# zero-hm-10-breakout.net
KiCad netlist of a schematic drawn in EAGLE
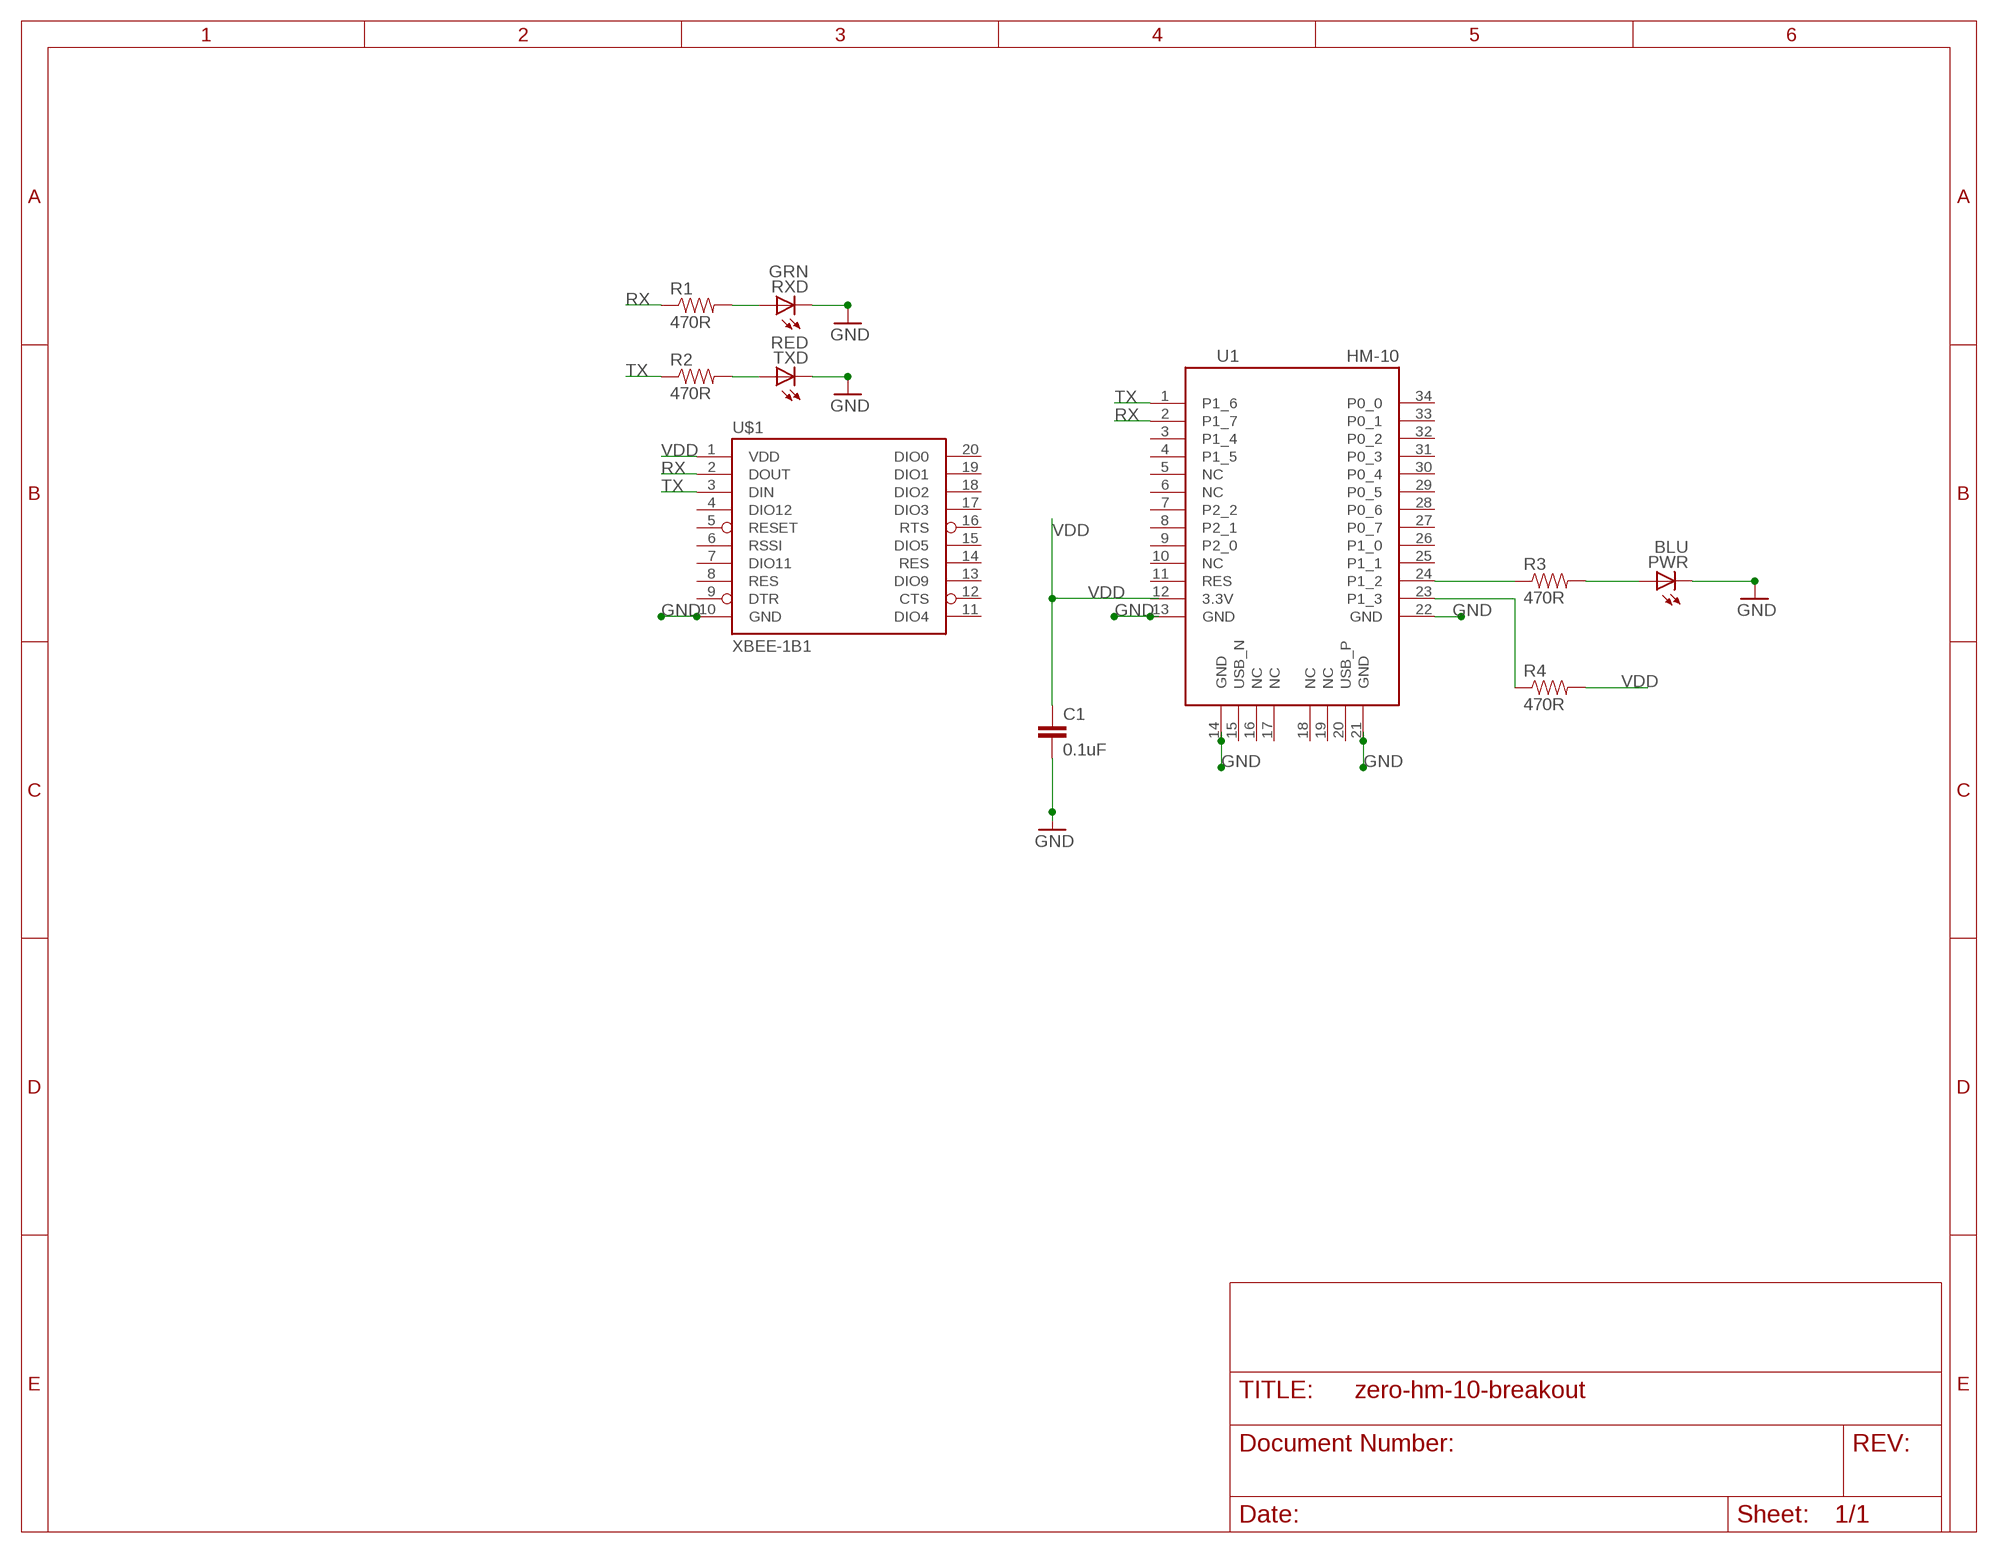
[diagram p0: schematic, sheet 1]

(export (version "E")
  (design (tool "Eeschema 10.0.6"))
  (components
    (comp (ref "C1")
      (value "0.1uF")
      (footprint "eagle-import:0603-CAP")
      (libsource (lib "eagle-import") (part "0.1UF-25V(+80/-20%)(0603)"))
    )
    (comp (ref "PWR")
      (value "BLU")
      (footprint "eagle-import:CHIPLED_0805")
      (libsource (lib "eagle-import") (part "LEDCHIPLED_0805"))
    )
    (comp (ref "R1")
      (value "470R")
      (footprint "eagle-import:0805")
      (libsource (lib "eagle-import") (part "0.3OHM-1/8W-1%(0805)"))
    )
    (comp (ref "R2")
      (value "470R")
      (footprint "eagle-import:0805")
      (libsource (lib "eagle-import") (part "0.3OHM-1/8W-1%(0805)"))
    )
    (comp (ref "R3")
      (value "470R")
      (footprint "eagle-import:0805")
      (libsource (lib "eagle-import") (part "0.3OHM-1/8W-1%(0805)"))
    )
    (comp (ref "R4")
      (value "470R")
      (footprint "eagle-import:0805")
      (libsource (lib "eagle-import") (part "0.3OHM-1/8W-1%(0805)"))
    )
    (comp (ref "RXD")
      (value "GRN")
      (footprint "eagle-import:CHIPLED_0805")
      (libsource (lib "eagle-import") (part "LEDCHIPLED_0805"))
    )
    (comp (ref "TXD")
      (value "RED")
      (footprint "eagle-import:CHIPLED_0805")
      (libsource (lib "eagle-import") (part "LEDCHIPLED_0805"))
    )
    (comp (ref "U$1")
      (value "XBEE-1B1")
      (footprint "eagle-import:XBEE-1")
      (libsource (lib "eagle-import") (part "XBEE-1B1"))
    )
    (comp (ref "U1")
      (value "HM-10")
      (footprint "eagle-import:HM-10")
      (libsource (lib "eagle-import") (part "HM-10"))
    )
  )
  (nets
    (net (code "1") (name "/RX") (class "Default")
      (node (ref "R1") (pin "1") (pinfunction "1_1") (pintype "passive"))
      (node (ref "U$1") (pin "2") (pinfunction "DOUT_2") (pintype "output"))
      (node (ref "U1") (pin "2") (pinfunction "P1_7_2") (pintype "bidirectional"))
    )
    (net (code "2") (name "/TX") (class "Default")
      (node (ref "R2") (pin "1") (pinfunction "1_1") (pintype "passive"))
      (node (ref "U$1") (pin "3") (pinfunction "DIN_3") (pintype "input"))
      (node (ref "U1") (pin "1") (pinfunction "P1_6_1") (pintype "bidirectional"))
    )
    (net (code "3") (name "/VDD") (class "Default")
      (node (ref "C1") (pin "1") (pinfunction "1_1") (pintype "passive"))
      (node (ref "R4") (pin "2") (pinfunction "2_2") (pintype "passive"))
      (node (ref "U$1") (pin "1") (pinfunction "VDD_1") (pintype "power_in"))
      (node (ref "U1") (pin "12") (pinfunction "3.3V_12") (pintype "bidirectional"))
    )
    (net (code "4") (name "GND") (class "Default")
      (node (ref "C1") (pin "2") (pinfunction "2_2") (pintype "passive"))
      (node (ref "PWR") (pin "C") (pinfunction "C_C") (pintype "passive"))
      (node (ref "RXD") (pin "C") (pinfunction "C_C") (pintype "passive"))
      (node (ref "TXD") (pin "C") (pinfunction "C_C") (pintype "passive"))
      (node (ref "U$1") (pin "10") (pinfunction "GND_10") (pintype "power_in"))
      (node (ref "U1") (pin "13") (pinfunction "GND_13") (pintype "bidirectional"))
      (node (ref "U1") (pin "14") (pinfunction "GND_14") (pintype "bidirectional"))
      (node (ref "U1") (pin "21") (pinfunction "GND_21") (pintype "bidirectional"))
      (node (ref "U1") (pin "22") (pinfunction "GND_22") (pintype "bidirectional"))
    )
    (net (code "5") (name "Net-(PWR-PadA)") (class "Default")
      (node (ref "PWR") (pin "A") (pinfunction "A_A") (pintype "passive"))
      (node (ref "R3") (pin "2") (pinfunction "2_2") (pintype "passive"))
    )
    (net (code "6") (name "Net-(R1-Pad2)") (class "Default")
      (node (ref "R1") (pin "2") (pinfunction "2_2") (pintype "passive"))
      (node (ref "RXD") (pin "A") (pinfunction "A_A") (pintype "passive"))
    )
    (net (code "7") (name "Net-(R2-Pad2)") (class "Default")
      (node (ref "R2") (pin "2") (pinfunction "2_2") (pintype "passive"))
      (node (ref "TXD") (pin "A") (pinfunction "A_A") (pintype "passive"))
    )
    (net (code "8") (name "Net-(U1-P1_2)") (class "Default")
      (node (ref "R3") (pin "1") (pinfunction "1_1") (pintype "passive"))
      (node (ref "U1") (pin "24") (pinfunction "P1_2_24") (pintype "bidirectional"))
    )
    (net (code "9") (name "Net-(U1-P1_3)") (class "Default")
      (node (ref "R4") (pin "1") (pinfunction "1_1") (pintype "passive"))
      (node (ref "U1") (pin "23") (pinfunction "P1_3_23") (pintype "bidirectional"))
    )
    (net (code "10") (name "unconnected-(U$1-CTS-Pad12)") (class "Default")
      (node (ref "U$1") (pin "12") (pinfunction "CTS_12") (pintype "output"))
    )
    (net (code "11") (name "unconnected-(U$1-DIO0-Pad20)") (class "Default")
      (node (ref "U$1") (pin "20") (pinfunction "DIO0_20") (pintype "bidirectional"))
    )
    (net (code "12") (name "unconnected-(U$1-DIO1-Pad19)") (class "Default")
      (node (ref "U$1") (pin "19") (pinfunction "DIO1_19") (pintype "bidirectional"))
    )
    (net (code "13") (name "unconnected-(U$1-DIO2-Pad18)") (class "Default")
      (node (ref "U$1") (pin "18") (pinfunction "DIO2_18") (pintype "bidirectional"))
    )
    (net (code "14") (name "unconnected-(U$1-DIO3-Pad17)") (class "Default")
      (node (ref "U$1") (pin "17") (pinfunction "DIO3_17") (pintype "bidirectional"))
    )
    (net (code "15") (name "unconnected-(U$1-DIO4-Pad11)") (class "Default")
      (node (ref "U$1") (pin "11") (pinfunction "DIO4_11") (pintype "bidirectional"))
    )
    (net (code "16") (name "unconnected-(U$1-DIO5-Pad15)") (class "Default")
      (node (ref "U$1") (pin "15") (pinfunction "DIO5_15") (pintype "bidirectional"))
    )
    (net (code "17") (name "unconnected-(U$1-DIO9-Pad13)") (class "Default")
      (node (ref "U$1") (pin "13") (pinfunction "DIO9_13") (pintype "bidirectional"))
    )
    (net (code "18") (name "unconnected-(U$1-DIO11-Pad7)") (class "Default")
      (node (ref "U$1") (pin "7") (pinfunction "DIO11_7") (pintype "bidirectional"))
    )
    (net (code "19") (name "unconnected-(U$1-DIO12-Pad4)") (class "Default")
      (node (ref "U$1") (pin "4") (pinfunction "DIO12_4") (pintype "bidirectional"))
    )
    (net (code "20") (name "unconnected-(U$1-DTR-Pad9)") (class "Default")
      (node (ref "U$1") (pin "9") (pinfunction "DTR_9") (pintype "bidirectional"))
    )
    (net (code "21") (name "unconnected-(U$1-RES-Pad8)") (class "Default")
      (node (ref "U$1") (pin "8") (pinfunction "RES_8") (pintype "bidirectional"))
    )
    (net (code "22") (name "unconnected-(U$1-RES-Pad14)") (class "Default")
      (node (ref "U$1") (pin "14") (pinfunction "RES_14") (pintype "bidirectional"))
    )
    (net (code "23") (name "unconnected-(U$1-RESET-Pad5)") (class "Default")
      (node (ref "U$1") (pin "5") (pinfunction "RESET_5") (pintype "input"))
    )
    (net (code "24") (name "unconnected-(U$1-RSSI-Pad6)") (class "Default")
      (node (ref "U$1") (pin "6") (pinfunction "RSSI_6") (pintype "bidirectional"))
    )
    (net (code "25") (name "unconnected-(U$1-RTS-Pad16)") (class "Default")
      (node (ref "U$1") (pin "16") (pinfunction "RTS_16") (pintype "input"))
    )
    (net (code "26") (name "unconnected-(U1-NC-Pad5)") (class "Default")
      (node (ref "U1") (pin "5") (pinfunction "NC_5") (pintype "bidirectional"))
    )
    (net (code "27") (name "unconnected-(U1-NC-Pad6)") (class "Default")
      (node (ref "U1") (pin "6") (pinfunction "NC_6") (pintype "bidirectional"))
    )
    (net (code "28") (name "unconnected-(U1-NC-Pad10)") (class "Default")
      (node (ref "U1") (pin "10") (pinfunction "NC_10") (pintype "bidirectional"))
    )
    (net (code "29") (name "unconnected-(U1-NC-Pad16)") (class "Default")
      (node (ref "U1") (pin "16") (pinfunction "NC_16") (pintype "bidirectional"))
    )
    (net (code "30") (name "unconnected-(U1-NC-Pad17)") (class "Default")
      (node (ref "U1") (pin "17") (pinfunction "NC_17") (pintype "bidirectional"))
    )
    (net (code "31") (name "unconnected-(U1-NC-Pad18)") (class "Default")
      (node (ref "U1") (pin "18") (pinfunction "NC_18") (pintype "bidirectional"))
    )
    (net (code "32") (name "unconnected-(U1-NC-Pad19)") (class "Default")
      (node (ref "U1") (pin "19") (pinfunction "NC_19") (pintype "bidirectional"))
    )
    (net (code "33") (name "unconnected-(U1-P0_0-Pad34)") (class "Default")
      (node (ref "U1") (pin "34") (pinfunction "P0_0_34") (pintype "bidirectional"))
    )
    (net (code "34") (name "unconnected-(U1-P0_1-Pad33)") (class "Default")
      (node (ref "U1") (pin "33") (pinfunction "P0_1_33") (pintype "bidirectional"))
    )
    (net (code "35") (name "unconnected-(U1-P0_2-Pad32)") (class "Default")
      (node (ref "U1") (pin "32") (pinfunction "P0_2_32") (pintype "bidirectional"))
    )
    (net (code "36") (name "unconnected-(U1-P0_3-Pad31)") (class "Default")
      (node (ref "U1") (pin "31") (pinfunction "P0_3_31") (pintype "bidirectional"))
    )
    (net (code "37") (name "unconnected-(U1-P0_4-Pad30)") (class "Default")
      (node (ref "U1") (pin "30") (pinfunction "P0_4_30") (pintype "bidirectional"))
    )
    (net (code "38") (name "unconnected-(U1-P0_5-Pad29)") (class "Default")
      (node (ref "U1") (pin "29") (pinfunction "P0_5_29") (pintype "bidirectional"))
    )
    (net (code "39") (name "unconnected-(U1-P0_6-Pad28)") (class "Default")
      (node (ref "U1") (pin "28") (pinfunction "P0_6_28") (pintype "bidirectional"))
    )
    (net (code "40") (name "unconnected-(U1-P0_7-Pad27)") (class "Default")
      (node (ref "U1") (pin "27") (pinfunction "P0_7_27") (pintype "bidirectional"))
    )
    (net (code "41") (name "unconnected-(U1-P1_0-Pad26)") (class "Default")
      (node (ref "U1") (pin "26") (pinfunction "P1_0_26") (pintype "bidirectional"))
    )
    (net (code "42") (name "unconnected-(U1-P1_1-Pad25)") (class "Default")
      (node (ref "U1") (pin "25") (pinfunction "P1_1_25") (pintype "bidirectional"))
    )
    (net (code "43") (name "unconnected-(U1-P1_4-Pad3)") (class "Default")
      (node (ref "U1") (pin "3") (pinfunction "P1_4_3") (pintype "bidirectional"))
    )
    (net (code "44") (name "unconnected-(U1-P1_5-Pad4)") (class "Default")
      (node (ref "U1") (pin "4") (pinfunction "P1_5_4") (pintype "bidirectional"))
    )
    (net (code "45") (name "unconnected-(U1-P2_0-Pad9)") (class "Default")
      (node (ref "U1") (pin "9") (pinfunction "P2_0_9") (pintype "bidirectional"))
    )
    (net (code "46") (name "unconnected-(U1-P2_1-Pad8)") (class "Default")
      (node (ref "U1") (pin "8") (pinfunction "P2_1_8") (pintype "bidirectional"))
    )
    (net (code "47") (name "unconnected-(U1-P2_2-Pad7)") (class "Default")
      (node (ref "U1") (pin "7") (pinfunction "P2_2_7") (pintype "bidirectional"))
    )
    (net (code "48") (name "unconnected-(U1-RES-Pad11)") (class "Default")
      (node (ref "U1") (pin "11") (pinfunction "RES_11") (pintype "bidirectional"))
    )
    (net (code "49") (name "unconnected-(U1-USB_N-Pad15)") (class "Default")
      (node (ref "U1") (pin "15") (pinfunction "USB_N_15") (pintype "bidirectional"))
    )
    (net (code "50") (name "unconnected-(U1-USB_P-Pad20)") (class "Default")
      (node (ref "U1") (pin "20") (pinfunction "USB_P_20") (pintype "bidirectional"))
    )
  )
)
